# MCU.net
KiCad netlist of a schematic drawn in Altium Designer
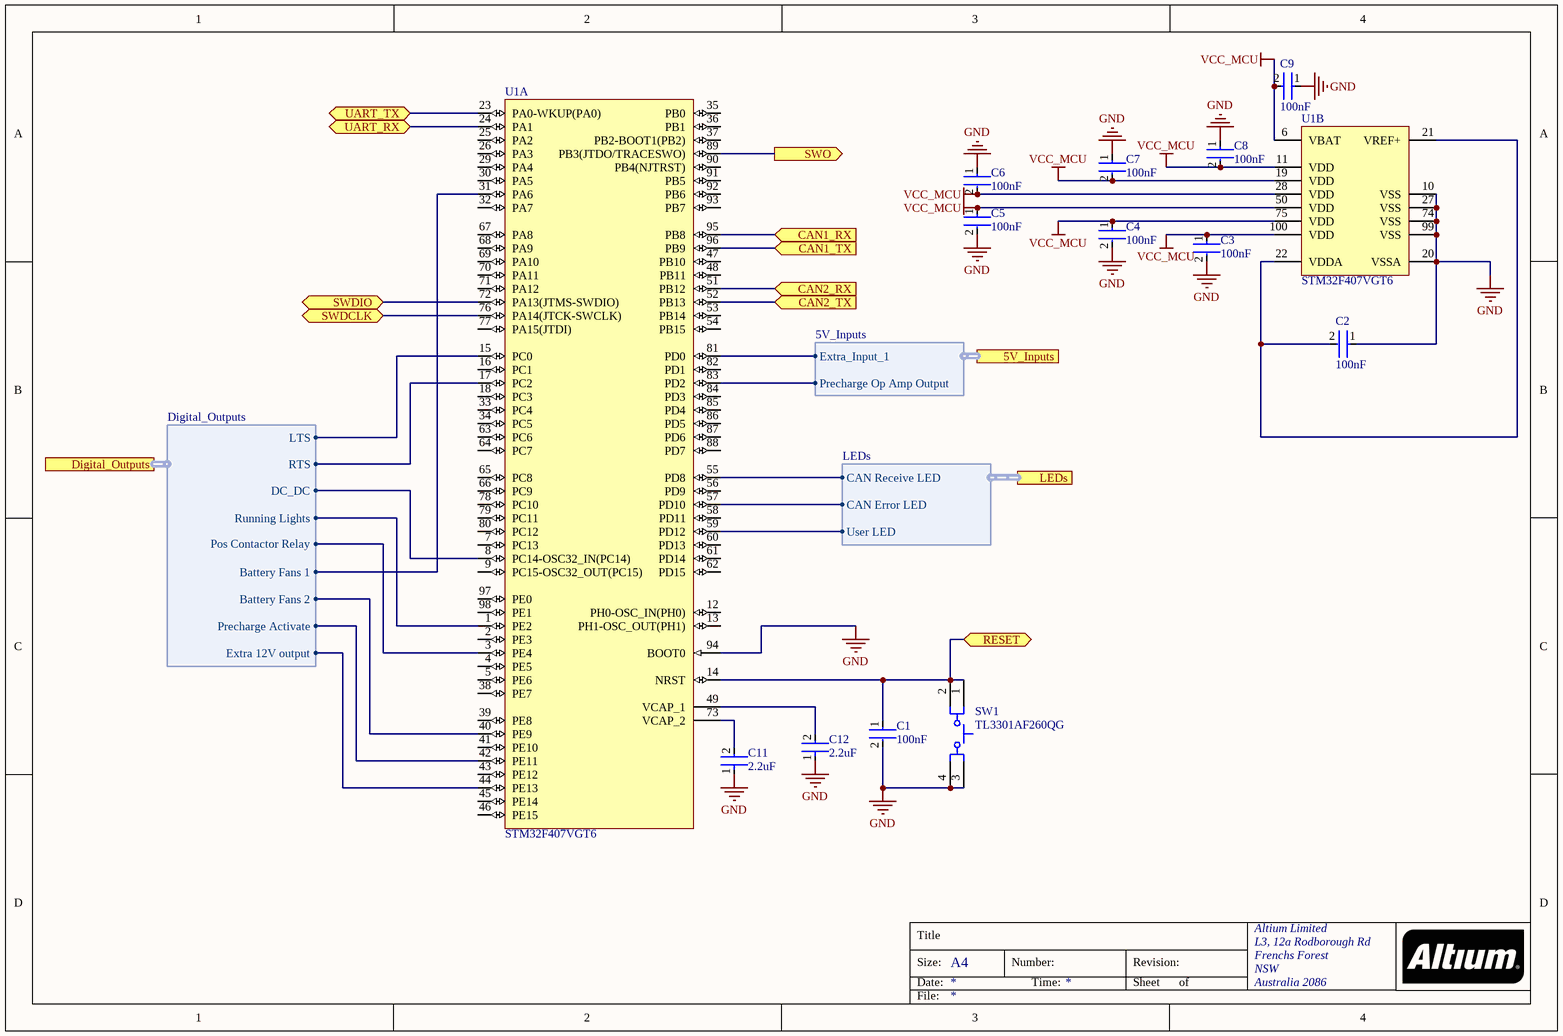
[diagram p0: MCU.SchDoc]

(export (version "E")
  (design (tool "Eeschema 10.0.6"))
  (components
    (comp (ref "C1")
      (value "100nF")
      (footprint "Kemet_C0603_IPC_A")
      (description "CAP CER 0.1UF 100NF 50V X7R 0603 C0603C104K5RACTU")
      (libsource (lib "UNK_Kemet_C0603C104K5RACTU_eec") (part "C0603C104K5RACTU"))
    )
    (comp (ref "C2")
      (value "100nF")
      (footprint "Kemet_C0603_IPC_A")
      (description "CAP CER 0.1UF 100NF 50V X7R 0603 C0603C104K5RACTU")
      (libsource (lib "UNK_Kemet_C0603C104K5RACTU_eec") (part "C0603C104K5RACTU"))
    )
    (comp (ref "C3")
      (value "100nF")
      (footprint "Kemet_C0603_IPC_A")
      (description "CAP CER 0.1UF 100NF 50V X7R 0603 C0603C104K5RACTU")
      (libsource (lib "UNK_Kemet_C0603C104K5RACTU_eec") (part "C0603C104K5RACTU"))
    )
    (comp (ref "C4")
      (value "100nF")
      (footprint "Kemet_C0603_IPC_A")
      (description "CAP CER 0.1UF 100NF 50V X7R 0603 C0603C104K5RACTU")
      (libsource (lib "UNK_Kemet_C0603C104K5RACTU_eec") (part "C0603C104K5RACTU"))
    )
    (comp (ref "C5")
      (value "100nF")
      (footprint "Kemet_C0603_IPC_A")
      (description "CAP CER 0.1UF 100NF 50V X7R 0603 C0603C104K5RACTU")
      (libsource (lib "UNK_Kemet_C0603C104K5RACTU_eec") (part "C0603C104K5RACTU"))
    )
    (comp (ref "C6")
      (value "100nF")
      (footprint "Kemet_C0603_IPC_A")
      (description "CAP CER 0.1UF 100NF 50V X7R 0603 C0603C104K5RACTU")
      (libsource (lib "UNK_Kemet_C0603C104K5RACTU_eec") (part "C0603C104K5RACTU"))
    )
    (comp (ref "C7")
      (value "100nF")
      (footprint "Kemet_C0603_IPC_A")
      (description "CAP CER 0.1UF 100NF 50V X7R 0603 C0603C104K5RACTU")
      (libsource (lib "UNK_Kemet_C0603C104K5RACTU_eec") (part "C0603C104K5RACTU"))
    )
    (comp (ref "C8")
      (value "100nF")
      (footprint "Kemet_C0603_IPC_A")
      (description "CAP CER 0.1UF 100NF 50V X7R 0603 C0603C104K5RACTU")
      (libsource (lib "UNK_Kemet_C0603C104K5RACTU_eec") (part "C0603C104K5RACTU"))
    )
    (comp (ref "C9")
      (value "100nF")
      (footprint "Kemet_C0603_IPC_A")
      (description "CAP CER 0.1UF 100NF 50V X7R 0603 C0603C104K5RACTU")
      (libsource (lib "UNK_Kemet_C0603C104K5RACTU_eec") (part "C0603C104K5RACTU"))
    )
    (comp (ref "C11")
      (value "2.2uF")
      (footprint "Yageo_CC0805-0.85_IPC_A")
      (description "2.2UF CC0805KKX7R6BB225")
      (libsource (lib "Cap_Yageo_CC0805KKX7R6BB225_eec") (part "CC0805KKX7R6BB225"))
    )
    (comp (ref "C12")
      (value "2.2uF")
      (footprint "Yageo_CC0805-0.85_IPC_A")
      (description "2.2UF CC0805KKX7R6BB225")
      (libsource (lib "Cap_Yageo_CC0805KKX7R6BB225_eec") (part "CC0805KKX7R6BB225"))
    )
    (comp (ref "SW1")
      (value "TL3301AF260QG")
      (footprint "ESWI-TL3301AF260QG_V")
      (description "Tactile Switch, SPST-NO, 50 mA, 12 V, -20 to 70 degC, 4-Pin SMD, RoHS, Tape and Reel")
      (fields (field (name "MANUFACTURER") "E-Switch"))
      (libsource (lib "Altium Content Vault") (part "SW-SPST-NO-4"))
    )
    (comp (ref "U1")
      (value "STM32F407VGT6")
      (footprint "STM-LQFP100_M")
      (fields (field (name "MANUFACTURER") "STMicroelectronics"))
      (libsource (lib "Altium Content Vault") (part "MC-ARM-STM32F40X_41X-SQ100"))
    )
  )
  (nets
    (net (code "4") (name "/Battery Fans 1") (class "Default")
      (node (ref "U1") (pin "31") (pinfunction "PA6_31") (pintype "bidirectional"))
    )
    (net (code "5") (name "/Battery Fans 2") (class "Default")
      (node (ref "U1") (pin "40") (pinfunction "PE9_40") (pintype "bidirectional"))
    )
    (net (code "6") (name "/CAN Error LED") (class "Default")
      (node (ref "U1") (pin "57") (pinfunction "PD10_57") (pintype "bidirectional"))
    )
    (net (code "7") (name "/CAN Receive LED") (class "Default")
      (node (ref "U1") (pin "55") (pinfunction "PD8_55") (pintype "bidirectional"))
    )
    (net (code "8") (name "/CAN1_RX") (class "Default")
      (node (ref "U1") (pin "95") (pinfunction "PB8_95") (pintype "bidirectional"))
    )
    (net (code "9") (name "/CAN1_TX") (class "Default")
      (node (ref "U1") (pin "96") (pinfunction "PB9_96") (pintype "bidirectional"))
    )
    (net (code "10") (name "/CAN2_RX") (class "Default")
      (node (ref "U1") (pin "51") (pinfunction "PB12_51") (pintype "bidirectional"))
    )
    (net (code "11") (name "/CAN2_TX") (class "Default")
      (node (ref "U1") (pin "52") (pinfunction "PB13_52") (pintype "bidirectional"))
    )
    (net (code "12") (name "/DC_DC") (class "Default")
      (node (ref "U1") (pin "8") (pinfunction "PC14-OSC32_IN(PC14)_8") (pintype "bidirectional"))
    )
    (net (code "13") (name "/Extra 12V output") (class "Default")
      (node (ref "U1") (pin "44") (pinfunction "PE13_44") (pintype "bidirectional"))
    )
    (net (code "14") (name "/Extra_Input_1") (class "Default")
      (node (ref "U1") (pin "81") (pinfunction "PD0_81") (pintype "bidirectional"))
    )
    (net (code "15") (name "/LTS") (class "Default")
      (node (ref "U1") (pin "15") (pinfunction "PC0_15") (pintype "bidirectional"))
    )
    (net (code "16") (name "/Pos Contactor Relay") (class "Default")
      (node (ref "U1") (pin "3") (pinfunction "PE4_3") (pintype "bidirectional"))
    )
    (net (code "17") (name "/Precharge Activate") (class "Default")
      (node (ref "U1") (pin "42") (pinfunction "PE11_42") (pintype "bidirectional"))
    )
    (net (code "18") (name "/Precharge Op Amp Output") (class "Default")
      (node (ref "U1") (pin "83") (pinfunction "PD2_83") (pintype "bidirectional"))
    )
    (net (code "19") (name "/RESET") (class "Default")
      (node (ref "C1") (pin "1") (pinfunction "1_1") (pintype "passive"))
      (node (ref "SW1") (pin "1") (pinfunction "1_1") (pintype "passive"))
      (node (ref "SW1") (pin "2") (pinfunction "2_2") (pintype "passive"))
      (node (ref "U1") (pin "14") (pinfunction "NRST_14") (pintype "bidirectional"))
    )
    (net (code "20") (name "/RTS") (class "Default")
      (node (ref "U1") (pin "17") (pinfunction "PC2_17") (pintype "bidirectional"))
    )
    (net (code "21") (name "/Running Lights") (class "Default")
      (node (ref "U1") (pin "1") (pinfunction "PE2_1") (pintype "bidirectional"))
    )
    (net (code "22") (name "/SWDCLK") (class "Default")
      (node (ref "U1") (pin "76") (pinfunction "PA14(JTCK-SWCLK)_76") (pintype "bidirectional"))
    )
    (net (code "23") (name "/SWDIO") (class "Default")
      (node (ref "U1") (pin "72") (pinfunction "PA13(JTMS-SWDIO)_72") (pintype "bidirectional"))
    )
    (net (code "24") (name "/SWO") (class "Default")
      (node (ref "U1") (pin "89") (pinfunction "PB3(JTDO/TRACESWO)_89") (pintype "bidirectional"))
    )
    (net (code "25") (name "/UART_RX") (class "Default")
      (node (ref "U1") (pin "24") (pinfunction "PA1_24") (pintype "bidirectional"))
    )
    (net (code "26") (name "/UART_TX") (class "Default")
      (node (ref "U1") (pin "23") (pinfunction "PA0-WKUP(PA0)_23") (pintype "bidirectional"))
    )
    (net (code "27") (name "/User LED") (class "Default")
      (node (ref "U1") (pin "59") (pinfunction "PD12_59") (pintype "bidirectional"))
    )
    (net (code "31") (name "GND") (class "Default")
      (node (ref "C1") (pin "2") (pinfunction "2_2") (pintype "passive"))
      (node (ref "C11") (pin "1") (pinfunction "1_1") (pintype "passive"))
      (node (ref "C12") (pin "1") (pinfunction "1_1") (pintype "passive"))
      (node (ref "C2") (pin "1") (pinfunction "1_1") (pintype "passive"))
      (node (ref "C3") (pin "2") (pinfunction "2_2") (pintype "passive"))
      (node (ref "C4") (pin "2") (pinfunction "2_2") (pintype "passive"))
      (node (ref "C5") (pin "2") (pinfunction "2_2") (pintype "passive"))
      (node (ref "C6") (pin "1") (pinfunction "1_1") (pintype "passive"))
      (node (ref "C7") (pin "1") (pinfunction "1_1") (pintype "passive"))
      (node (ref "C8") (pin "1") (pinfunction "1_1") (pintype "passive"))
      (node (ref "C9") (pin "1") (pinfunction "1_1") (pintype "passive"))
      (node (ref "SW1") (pin "3") (pinfunction "3_3") (pintype "passive"))
      (node (ref "SW1") (pin "4") (pinfunction "4_4") (pintype "passive"))
      (node (ref "U1") (pin "10") (pinfunction "VSS_10") (pintype "power_in"))
      (node (ref "U1") (pin "20") (pinfunction "VSSA_20") (pintype "power_in"))
      (node (ref "U1") (pin "27") (pinfunction "VSS_27") (pintype "power_in"))
      (node (ref "U1") (pin "74") (pinfunction "VSS_74") (pintype "power_in"))
      (node (ref "U1") (pin "94") (pinfunction "BOOT0_94") (pintype "input"))
      (node (ref "U1") (pin "99") (pinfunction "VSS_99") (pintype "power_in"))
    )
    (net (code "32") (name "Net-(U1A-VCAP_1)") (class "Default")
      (node (ref "C12") (pin "2") (pinfunction "2_2") (pintype "passive"))
      (node (ref "U1") (pin "49") (pinfunction "VCAP_1_49") (pintype "power_in"))
    )
    (net (code "33") (name "Net-(U1A-VCAP_2)") (class "Default")
      (node (ref "C11") (pin "2") (pinfunction "2_2") (pintype "passive"))
      (node (ref "U1") (pin "73") (pinfunction "VCAP_2_73") (pintype "power_in"))
    )
    (net (code "34") (name "Net-(U1B-VDDA)") (class "Default")
      (node (ref "C2") (pin "2") (pinfunction "2_2") (pintype "passive"))
      (node (ref "U1") (pin "21") (pinfunction "VREF+_21") (pintype "power_in"))
      (node (ref "U1") (pin "22") (pinfunction "VDDA_22") (pintype "power_in"))
    )
    (net (code "35") (name "VCC_MCU") (class "Default")
      (node (ref "C3") (pin "1") (pinfunction "1_1") (pintype "passive"))
      (node (ref "C4") (pin "1") (pinfunction "1_1") (pintype "passive"))
      (node (ref "C5") (pin "1") (pinfunction "1_1") (pintype "passive"))
      (node (ref "C6") (pin "2") (pinfunction "2_2") (pintype "passive"))
      (node (ref "C7") (pin "2") (pinfunction "2_2") (pintype "passive"))
      (node (ref "C8") (pin "2") (pinfunction "2_2") (pintype "passive"))
      (node (ref "C9") (pin "2") (pinfunction "2_2") (pintype "passive"))
      (node (ref "U1") (pin "100") (pinfunction "VDD_100") (pintype "power_in"))
      (node (ref "U1") (pin "11") (pinfunction "VDD_11") (pintype "power_in"))
      (node (ref "U1") (pin "19") (pinfunction "VDD_19") (pintype "power_in"))
      (node (ref "U1") (pin "28") (pinfunction "VDD_28") (pintype "power_in"))
      (node (ref "U1") (pin "50") (pinfunction "VDD_50") (pintype "power_in"))
      (node (ref "U1") (pin "6") (pinfunction "VBAT_6") (pintype "power_in"))
      (node (ref "U1") (pin "75") (pinfunction "VDD_75") (pintype "power_in"))
    )
    (net (code "36") (name "unconnected-(U1A-PA2-Pad25)") (class "Default")
      (node (ref "U1") (pin "25") (pinfunction "PA2_25") (pintype "bidirectional"))
    )
    (net (code "37") (name "unconnected-(U1A-PA3-Pad26)") (class "Default")
      (node (ref "U1") (pin "26") (pinfunction "PA3_26") (pintype "bidirectional"))
    )
    (net (code "38") (name "unconnected-(U1A-PA4-Pad29)") (class "Default")
      (node (ref "U1") (pin "29") (pinfunction "PA4_29") (pintype "bidirectional"))
    )
    (net (code "39") (name "unconnected-(U1A-PA5-Pad30)") (class "Default")
      (node (ref "U1") (pin "30") (pinfunction "PA5_30") (pintype "bidirectional"))
    )
    (net (code "40") (name "unconnected-(U1A-PA7-Pad32)") (class "Default")
      (node (ref "U1") (pin "32") (pinfunction "PA7_32") (pintype "bidirectional"))
    )
    (net (code "41") (name "unconnected-(U1A-PA8-Pad67)") (class "Default")
      (node (ref "U1") (pin "67") (pinfunction "PA8_67") (pintype "bidirectional"))
    )
    (net (code "42") (name "unconnected-(U1A-PA9-Pad68)") (class "Default")
      (node (ref "U1") (pin "68") (pinfunction "PA9_68") (pintype "bidirectional"))
    )
    (net (code "43") (name "unconnected-(U1A-PA10-Pad69)") (class "Default")
      (node (ref "U1") (pin "69") (pinfunction "PA10_69") (pintype "bidirectional"))
    )
    (net (code "44") (name "unconnected-(U1A-PA11-Pad70)") (class "Default")
      (node (ref "U1") (pin "70") (pinfunction "PA11_70") (pintype "bidirectional"))
    )
    (net (code "45") (name "unconnected-(U1A-PA12-Pad71)") (class "Default")
      (node (ref "U1") (pin "71") (pinfunction "PA12_71") (pintype "bidirectional"))
    )
    (net (code "46") (name "unconnected-(U1A-PA15(JTDI)-Pad77)") (class "Default")
      (node (ref "U1") (pin "77") (pinfunction "PA15(JTDI)_77") (pintype "bidirectional"))
    )
    (net (code "47") (name "unconnected-(U1A-PB0-Pad35)") (class "Default")
      (node (ref "U1") (pin "35") (pinfunction "PB0_35") (pintype "bidirectional"))
    )
    (net (code "48") (name "unconnected-(U1A-PB1-Pad36)") (class "Default")
      (node (ref "U1") (pin "36") (pinfunction "PB1_36") (pintype "bidirectional"))
    )
    (net (code "49") (name "unconnected-(U1A-PB2-BOOT1(PB2)-Pad37)") (class "Default")
      (node (ref "U1") (pin "37") (pinfunction "PB2-BOOT1(PB2)_37") (pintype "bidirectional"))
    )
    (net (code "50") (name "unconnected-(U1A-PB4(NJTRST)-Pad90)") (class "Default")
      (node (ref "U1") (pin "90") (pinfunction "PB4(NJTRST)_90") (pintype "bidirectional"))
    )
    (net (code "51") (name "unconnected-(U1A-PB5-Pad91)") (class "Default")
      (node (ref "U1") (pin "91") (pinfunction "PB5_91") (pintype "bidirectional"))
    )
    (net (code "52") (name "unconnected-(U1A-PB6-Pad92)") (class "Default")
      (node (ref "U1") (pin "92") (pinfunction "PB6_92") (pintype "bidirectional"))
    )
    (net (code "53") (name "unconnected-(U1A-PB7-Pad93)") (class "Default")
      (node (ref "U1") (pin "93") (pinfunction "PB7_93") (pintype "bidirectional"))
    )
    (net (code "54") (name "unconnected-(U1A-PB10-Pad47)") (class "Default")
      (node (ref "U1") (pin "47") (pinfunction "PB10_47") (pintype "bidirectional"))
    )
    (net (code "55") (name "unconnected-(U1A-PB11-Pad48)") (class "Default")
      (node (ref "U1") (pin "48") (pinfunction "PB11_48") (pintype "bidirectional"))
    )
    (net (code "56") (name "unconnected-(U1A-PB14-Pad53)") (class "Default")
      (node (ref "U1") (pin "53") (pinfunction "PB14_53") (pintype "bidirectional"))
    )
    (net (code "57") (name "unconnected-(U1A-PB15-Pad54)") (class "Default")
      (node (ref "U1") (pin "54") (pinfunction "PB15_54") (pintype "bidirectional"))
    )
    (net (code "58") (name "unconnected-(U1A-PC1-Pad16)") (class "Default")
      (node (ref "U1") (pin "16") (pinfunction "PC1_16") (pintype "bidirectional"))
    )
    (net (code "59") (name "unconnected-(U1A-PC3-Pad18)") (class "Default")
      (node (ref "U1") (pin "18") (pinfunction "PC3_18") (pintype "bidirectional"))
    )
    (net (code "60") (name "unconnected-(U1A-PC4-Pad33)") (class "Default")
      (node (ref "U1") (pin "33") (pinfunction "PC4_33") (pintype "bidirectional"))
    )
    (net (code "61") (name "unconnected-(U1A-PC5-Pad34)") (class "Default")
      (node (ref "U1") (pin "34") (pinfunction "PC5_34") (pintype "bidirectional"))
    )
    (net (code "62") (name "unconnected-(U1A-PC6-Pad63)") (class "Default")
      (node (ref "U1") (pin "63") (pinfunction "PC6_63") (pintype "bidirectional"))
    )
    (net (code "63") (name "unconnected-(U1A-PC7-Pad64)") (class "Default")
      (node (ref "U1") (pin "64") (pinfunction "PC7_64") (pintype "bidirectional"))
    )
    (net (code "64") (name "unconnected-(U1A-PC8-Pad65)") (class "Default")
      (node (ref "U1") (pin "65") (pinfunction "PC8_65") (pintype "bidirectional"))
    )
    (net (code "65") (name "unconnected-(U1A-PC9-Pad66)") (class "Default")
      (node (ref "U1") (pin "66") (pinfunction "PC9_66") (pintype "bidirectional"))
    )
    (net (code "66") (name "unconnected-(U1A-PC10-Pad78)") (class "Default")
      (node (ref "U1") (pin "78") (pinfunction "PC10_78") (pintype "bidirectional"))
    )
    (net (code "67") (name "unconnected-(U1A-PC11-Pad79)") (class "Default")
      (node (ref "U1") (pin "79") (pinfunction "PC11_79") (pintype "bidirectional"))
    )
    (net (code "68") (name "unconnected-(U1A-PC12-Pad80)") (class "Default")
      (node (ref "U1") (pin "80") (pinfunction "PC12_80") (pintype "bidirectional"))
    )
    (net (code "69") (name "unconnected-(U1A-PC13-Pad7)") (class "Default")
      (node (ref "U1") (pin "7") (pinfunction "PC13_7") (pintype "bidirectional"))
    )
    (net (code "70") (name "unconnected-(U1A-PC15-OSC32_OUT(PC15)-Pad9)") (class "Default")
      (node (ref "U1") (pin "9") (pinfunction "PC15-OSC32_OUT(PC15)_9") (pintype "bidirectional"))
    )
    (net (code "71") (name "unconnected-(U1A-PD1-Pad82)") (class "Default")
      (node (ref "U1") (pin "82") (pinfunction "PD1_82") (pintype "bidirectional"))
    )
    (net (code "72") (name "unconnected-(U1A-PD3-Pad84)") (class "Default")
      (node (ref "U1") (pin "84") (pinfunction "PD3_84") (pintype "bidirectional"))
    )
    (net (code "73") (name "unconnected-(U1A-PD4-Pad85)") (class "Default")
      (node (ref "U1") (pin "85") (pinfunction "PD4_85") (pintype "bidirectional"))
    )
    (net (code "74") (name "unconnected-(U1A-PD5-Pad86)") (class "Default")
      (node (ref "U1") (pin "86") (pinfunction "PD5_86") (pintype "bidirectional"))
    )
    (net (code "75") (name "unconnected-(U1A-PD6-Pad87)") (class "Default")
      (node (ref "U1") (pin "87") (pinfunction "PD6_87") (pintype "bidirectional"))
    )
    (net (code "76") (name "unconnected-(U1A-PD7-Pad88)") (class "Default")
      (node (ref "U1") (pin "88") (pinfunction "PD7_88") (pintype "bidirectional"))
    )
    (net (code "77") (name "unconnected-(U1A-PD9-Pad56)") (class "Default")
      (node (ref "U1") (pin "56") (pinfunction "PD9_56") (pintype "bidirectional"))
    )
    (net (code "78") (name "unconnected-(U1A-PD11-Pad58)") (class "Default")
      (node (ref "U1") (pin "58") (pinfunction "PD11_58") (pintype "bidirectional"))
    )
    (net (code "79") (name "unconnected-(U1A-PD13-Pad60)") (class "Default")
      (node (ref "U1") (pin "60") (pinfunction "PD13_60") (pintype "bidirectional"))
    )
    (net (code "80") (name "unconnected-(U1A-PD14-Pad61)") (class "Default")
      (node (ref "U1") (pin "61") (pinfunction "PD14_61") (pintype "bidirectional"))
    )
    (net (code "81") (name "unconnected-(U1A-PD15-Pad62)") (class "Default")
      (node (ref "U1") (pin "62") (pinfunction "PD15_62") (pintype "bidirectional"))
    )
    (net (code "82") (name "unconnected-(U1A-PE0-Pad97)") (class "Default")
      (node (ref "U1") (pin "97") (pinfunction "PE0_97") (pintype "bidirectional"))
    )
    (net (code "83") (name "unconnected-(U1A-PE1-Pad98)") (class "Default")
      (node (ref "U1") (pin "98") (pinfunction "PE1_98") (pintype "bidirectional"))
    )
    (net (code "84") (name "unconnected-(U1A-PE3-Pad2)") (class "Default")
      (node (ref "U1") (pin "2") (pinfunction "PE3_2") (pintype "bidirectional"))
    )
    (net (code "85") (name "unconnected-(U1A-PE5-Pad4)") (class "Default")
      (node (ref "U1") (pin "4") (pinfunction "PE5_4") (pintype "bidirectional"))
    )
    (net (code "86") (name "unconnected-(U1A-PE6-Pad5)") (class "Default")
      (node (ref "U1") (pin "5") (pinfunction "PE6_5") (pintype "bidirectional"))
    )
    (net (code "87") (name "unconnected-(U1A-PE7-Pad38)") (class "Default")
      (node (ref "U1") (pin "38") (pinfunction "PE7_38") (pintype "bidirectional"))
    )
    (net (code "88") (name "unconnected-(U1A-PE8-Pad39)") (class "Default")
      (node (ref "U1") (pin "39") (pinfunction "PE8_39") (pintype "bidirectional"))
    )
    (net (code "89") (name "unconnected-(U1A-PE10-Pad41)") (class "Default")
      (node (ref "U1") (pin "41") (pinfunction "PE10_41") (pintype "bidirectional"))
    )
    (net (code "90") (name "unconnected-(U1A-PE12-Pad43)") (class "Default")
      (node (ref "U1") (pin "43") (pinfunction "PE12_43") (pintype "bidirectional"))
    )
    (net (code "91") (name "unconnected-(U1A-PE14-Pad45)") (class "Default")
      (node (ref "U1") (pin "45") (pinfunction "PE14_45") (pintype "bidirectional"))
    )
    (net (code "92") (name "unconnected-(U1A-PE15-Pad46)") (class "Default")
      (node (ref "U1") (pin "46") (pinfunction "PE15_46") (pintype "bidirectional"))
    )
    (net (code "93") (name "unconnected-(U1A-PH0-OSC_IN(PH0)-Pad12)") (class "Default")
      (node (ref "U1") (pin "12") (pinfunction "PH0-OSC_IN(PH0)_12") (pintype "bidirectional"))
    )
    (net (code "94") (name "unconnected-(U1A-PH1-OSC_OUT(PH1)-Pad13)") (class "Default")
      (node (ref "U1") (pin "13") (pinfunction "PH1-OSC_OUT(PH1)_13") (pintype "bidirectional"))
    )
  )
)
